# norlogic.net
KiCad netlist of a schematic drawn in EAGLE
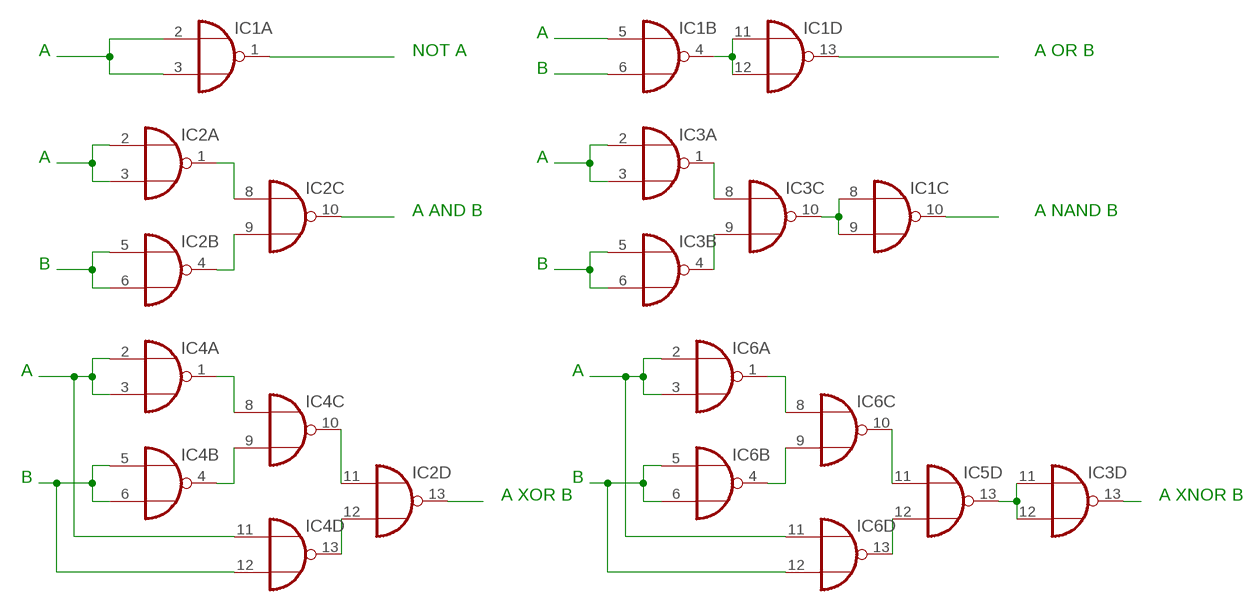
[diagram p0: schematic, sheet 1]

(export (version "E")
  (design (tool "Eeschema 10.0.6"))
  (components
    (comp (ref "IC1")
      (value "74AC02N")
      (footprint "eagle-import:DIL14")
      (libsource (lib "eagle-import") (part "7402NAC"))
    )
    (comp (ref "IC2")
      (value "74AC02N")
      (footprint "eagle-import:DIL14")
      (libsource (lib "eagle-import") (part "7402NAC"))
    )
    (comp (ref "IC3")
      (value "74AC02N")
      (footprint "eagle-import:DIL14")
      (libsource (lib "eagle-import") (part "7402NAC"))
    )
    (comp (ref "IC4")
      (value "74AC02N")
      (footprint "eagle-import:DIL14")
      (libsource (lib "eagle-import") (part "7402NAC"))
    )
    (comp (ref "IC5")
      (value "74AC02N")
      (footprint "eagle-import:DIL14")
      (libsource (lib "eagle-import") (part "7402NAC"))
    )
    (comp (ref "IC6")
      (value "74AC02N")
      (footprint "eagle-import:DIL14")
      (libsource (lib "eagle-import") (part "7402NAC"))
    )
  )
  (nets
    (net (code "1") (name "Net-(IC1A-I0)") (class "Default")
      (node (ref "IC1") (pin "2") (pinfunction "I0_2") (pintype "input"))
      (node (ref "IC1") (pin "3") (pinfunction "I1_3") (pintype "input"))
    )
    (net (code "2") (name "Net-(IC1B-O)") (class "Default")
      (node (ref "IC1") (pin "11") (pinfunction "I0_11") (pintype "input"))
      (node (ref "IC1") (pin "12") (pinfunction "I1_12") (pintype "input"))
      (node (ref "IC1") (pin "4") (pinfunction "O_4") (pintype "output"))
    )
    (net (code "3") (name "Net-(IC1C-I0)") (class "Default")
      (node (ref "IC1") (pin "8") (pinfunction "I0_8") (pintype "input"))
      (node (ref "IC1") (pin "9") (pinfunction "I1_9") (pintype "input"))
      (node (ref "IC3") (pin "10") (pinfunction "O_10") (pintype "output"))
    )
    (net (code "4") (name "Net-(IC2A-I0)") (class "Default")
      (node (ref "IC2") (pin "2") (pinfunction "I0_2") (pintype "input"))
      (node (ref "IC2") (pin "3") (pinfunction "I1_3") (pintype "input"))
    )
    (net (code "5") (name "Net-(IC2A-O)") (class "Default")
      (node (ref "IC2") (pin "1") (pinfunction "O_1") (pintype "output"))
      (node (ref "IC2") (pin "8") (pinfunction "I0_8") (pintype "input"))
    )
    (net (code "6") (name "Net-(IC2B-I0)") (class "Default")
      (node (ref "IC2") (pin "5") (pinfunction "I0_5") (pintype "input"))
      (node (ref "IC2") (pin "6") (pinfunction "I1_6") (pintype "input"))
    )
    (net (code "7") (name "Net-(IC2B-O)") (class "Default")
      (node (ref "IC2") (pin "4") (pinfunction "O_4") (pintype "output"))
      (node (ref "IC2") (pin "9") (pinfunction "I1_9") (pintype "input"))
    )
    (net (code "8") (name "Net-(IC2D-I0)") (class "Default")
      (node (ref "IC2") (pin "11") (pinfunction "I0_11") (pintype "input"))
      (node (ref "IC4") (pin "10") (pinfunction "O_10") (pintype "output"))
    )
    (net (code "9") (name "Net-(IC2D-I1)") (class "Default")
      (node (ref "IC2") (pin "12") (pinfunction "I1_12") (pintype "input"))
      (node (ref "IC4") (pin "13") (pinfunction "O_13") (pintype "output"))
    )
    (net (code "10") (name "Net-(IC3A-I0)") (class "Default")
      (node (ref "IC3") (pin "2") (pinfunction "I0_2") (pintype "input"))
      (node (ref "IC3") (pin "3") (pinfunction "I1_3") (pintype "input"))
    )
    (net (code "11") (name "Net-(IC3A-O)") (class "Default")
      (node (ref "IC3") (pin "1") (pinfunction "O_1") (pintype "output"))
      (node (ref "IC3") (pin "8") (pinfunction "I0_8") (pintype "input"))
    )
    (net (code "12") (name "Net-(IC3B-I0)") (class "Default")
      (node (ref "IC3") (pin "5") (pinfunction "I0_5") (pintype "input"))
      (node (ref "IC3") (pin "6") (pinfunction "I1_6") (pintype "input"))
    )
    (net (code "13") (name "Net-(IC3B-O)") (class "Default")
      (node (ref "IC3") (pin "4") (pinfunction "O_4") (pintype "output"))
      (node (ref "IC3") (pin "9") (pinfunction "I1_9") (pintype "input"))
    )
    (net (code "14") (name "Net-(IC3D-I0)") (class "Default")
      (node (ref "IC3") (pin "11") (pinfunction "I0_11") (pintype "input"))
      (node (ref "IC3") (pin "12") (pinfunction "I1_12") (pintype "input"))
      (node (ref "IC5") (pin "13") (pinfunction "O_13") (pintype "output"))
    )
    (net (code "15") (name "Net-(IC4A-I0)") (class "Default")
      (node (ref "IC4") (pin "11") (pinfunction "I0_11") (pintype "input"))
      (node (ref "IC4") (pin "2") (pinfunction "I0_2") (pintype "input"))
      (node (ref "IC4") (pin "3") (pinfunction "I1_3") (pintype "input"))
    )
    (net (code "16") (name "Net-(IC4A-O)") (class "Default")
      (node (ref "IC4") (pin "1") (pinfunction "O_1") (pintype "output"))
      (node (ref "IC4") (pin "8") (pinfunction "I0_8") (pintype "input"))
    )
    (net (code "17") (name "Net-(IC4B-I0)") (class "Default")
      (node (ref "IC4") (pin "12") (pinfunction "I1_12") (pintype "input"))
      (node (ref "IC4") (pin "5") (pinfunction "I0_5") (pintype "input"))
      (node (ref "IC4") (pin "6") (pinfunction "I1_6") (pintype "input"))
    )
    (net (code "18") (name "Net-(IC4B-O)") (class "Default")
      (node (ref "IC4") (pin "4") (pinfunction "O_4") (pintype "output"))
      (node (ref "IC4") (pin "9") (pinfunction "I1_9") (pintype "input"))
    )
    (net (code "19") (name "Net-(IC5D-I0)") (class "Default")
      (node (ref "IC5") (pin "11") (pinfunction "I0_11") (pintype "input"))
      (node (ref "IC6") (pin "10") (pinfunction "O_10") (pintype "output"))
    )
    (net (code "20") (name "Net-(IC5D-I1)") (class "Default")
      (node (ref "IC5") (pin "12") (pinfunction "I1_12") (pintype "input"))
      (node (ref "IC6") (pin "13") (pinfunction "O_13") (pintype "output"))
    )
    (net (code "21") (name "Net-(IC6A-I0)") (class "Default")
      (node (ref "IC6") (pin "11") (pinfunction "I0_11") (pintype "input"))
      (node (ref "IC6") (pin "2") (pinfunction "I0_2") (pintype "input"))
      (node (ref "IC6") (pin "3") (pinfunction "I1_3") (pintype "input"))
    )
    (net (code "22") (name "Net-(IC6A-O)") (class "Default")
      (node (ref "IC6") (pin "1") (pinfunction "O_1") (pintype "output"))
      (node (ref "IC6") (pin "8") (pinfunction "I0_8") (pintype "input"))
    )
    (net (code "23") (name "Net-(IC6B-I0)") (class "Default")
      (node (ref "IC6") (pin "12") (pinfunction "I1_12") (pintype "input"))
      (node (ref "IC6") (pin "5") (pinfunction "I0_5") (pintype "input"))
      (node (ref "IC6") (pin "6") (pinfunction "I1_6") (pintype "input"))
    )
    (net (code "24") (name "Net-(IC6B-O)") (class "Default")
      (node (ref "IC6") (pin "4") (pinfunction "O_4") (pintype "output"))
      (node (ref "IC6") (pin "9") (pinfunction "I1_9") (pintype "input"))
    )
    (net (code "25") (name "unconnected-(IC1A-O-Pad1)") (class "Default")
      (node (ref "IC1") (pin "1") (pinfunction "O_1") (pintype "output"))
    )
    (net (code "26") (name "unconnected-(IC1B-I0-Pad5)") (class "Default")
      (node (ref "IC1") (pin "5") (pinfunction "I0_5") (pintype "input"))
    )
    (net (code "27") (name "unconnected-(IC1B-I1-Pad6)") (class "Default")
      (node (ref "IC1") (pin "6") (pinfunction "I1_6") (pintype "input"))
    )
    (net (code "28") (name "unconnected-(IC1C-O-Pad10)") (class "Default")
      (node (ref "IC1") (pin "10") (pinfunction "O_10") (pintype "output"))
    )
    (net (code "29") (name "unconnected-(IC1D-O-Pad13)") (class "Default")
      (node (ref "IC1") (pin "13") (pinfunction "O_13") (pintype "output"))
    )
    (net (code "30") (name "unconnected-(IC2C-O-Pad10)") (class "Default")
      (node (ref "IC2") (pin "10") (pinfunction "O_10") (pintype "output"))
    )
    (net (code "31") (name "unconnected-(IC2D-O-Pad13)") (class "Default")
      (node (ref "IC2") (pin "13") (pinfunction "O_13") (pintype "output"))
    )
    (net (code "32") (name "unconnected-(IC3D-O-Pad13)") (class "Default")
      (node (ref "IC3") (pin "13") (pinfunction "O_13") (pintype "output"))
    )
  )
)
